# v1_0.net
KiCad netlist of a schematic drawn in Altium Designer
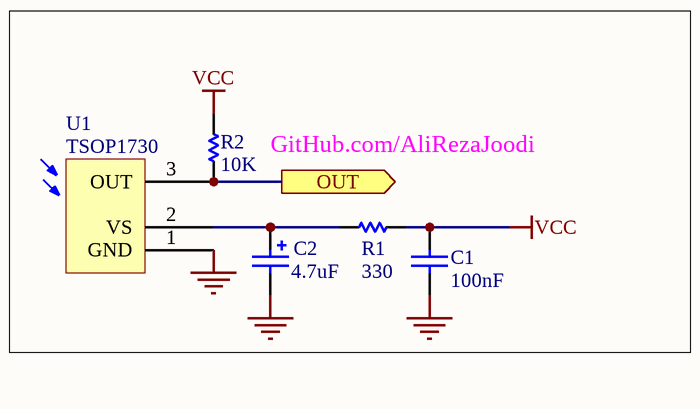
[diagram p0: v1.0.SchDoc]

(export (version "E")
  (design (tool "Eeschema 10.0.6"))
  (components
    (comp (ref "C1")
      (value "100nF")
      (footprint "CAPNTO2.54-3.05x1.78A")
      (description "Capacitor")
      (fields (field (name "MANUFACTURER") "Generic Components") (field (name "PUBLISHER") "Altium Limited"))
      (libsource (lib "Miscellaneous Devices") (part "Cap"))
    )
    (comp (ref "C2")
      (value "4.7uF")
      (footprint "CAPPR2.5-6.3x5")
      (description "Polarized Capacitor (Radial)")
      (fields (field (name "MANUFACTURER") "Generic Components") (field (name "PUBLISHER") "Altium Limited"))
      (libsource (lib "Miscellaneous Devices") (part "Cap Pol1"))
    )
    (comp (ref "R1")
      (value "330")
      (footprint "R_THD_AXIAL0.4(1/4W)")
      (description "Resistor")
      (libsource (lib "Passive") (part "Resistor"))
    )
    (comp (ref "R2")
      (value "10K")
      (footprint "R_THD_AXIAL0.4(1/4W)")
      (description "Resistor")
      (libsource (lib "Passive") (part "Resistor"))
    )
    (comp (ref "U1")
      (value "TSOP1730")
      (footprint "IR10")
      (description "IR receiver module for remote control")
      (libsource (lib "PicPars.com_usefully_Library") (part "IR Module"))
    )
  )
  (nets
    (net (code "1") (name "/OUT") (class "Default")
      (node (ref "R2") (pin "2") (pinfunction "2_2") (pintype "passive"))
      (node (ref "U1") (pin "3") (pinfunction "OUT_3") (pintype "passive"))
    )
    (net (code "2") (name "GND") (class "Default")
      (node (ref "C1") (pin "1") (pinfunction "1_1") (pintype "passive"))
      (node (ref "C2") (pin "2") (pinfunction "2_2") (pintype "passive"))
      (node (ref "U1") (pin "1") (pinfunction "GND_1") (pintype "passive"))
    )
    (net (code "3") (name "Net-(U1-VS)") (class "Default")
      (node (ref "C2") (pin "1") (pinfunction "1_1") (pintype "passive"))
      (node (ref "R1") (pin "1") (pinfunction "1_1") (pintype "passive"))
      (node (ref "U1") (pin "2") (pinfunction "VS_2") (pintype "passive"))
    )
    (net (code "4") (name "VCC") (class "Default")
      (node (ref "C1") (pin "2") (pinfunction "2_2") (pintype "passive"))
      (node (ref "R1") (pin "2") (pinfunction "2_2") (pintype "passive"))
      (node (ref "R2") (pin "1") (pinfunction "1_1") (pintype "passive"))
    )
  )
)
